# MicroSDcard.net
KiCad netlist of a schematic drawn in Altium Designer
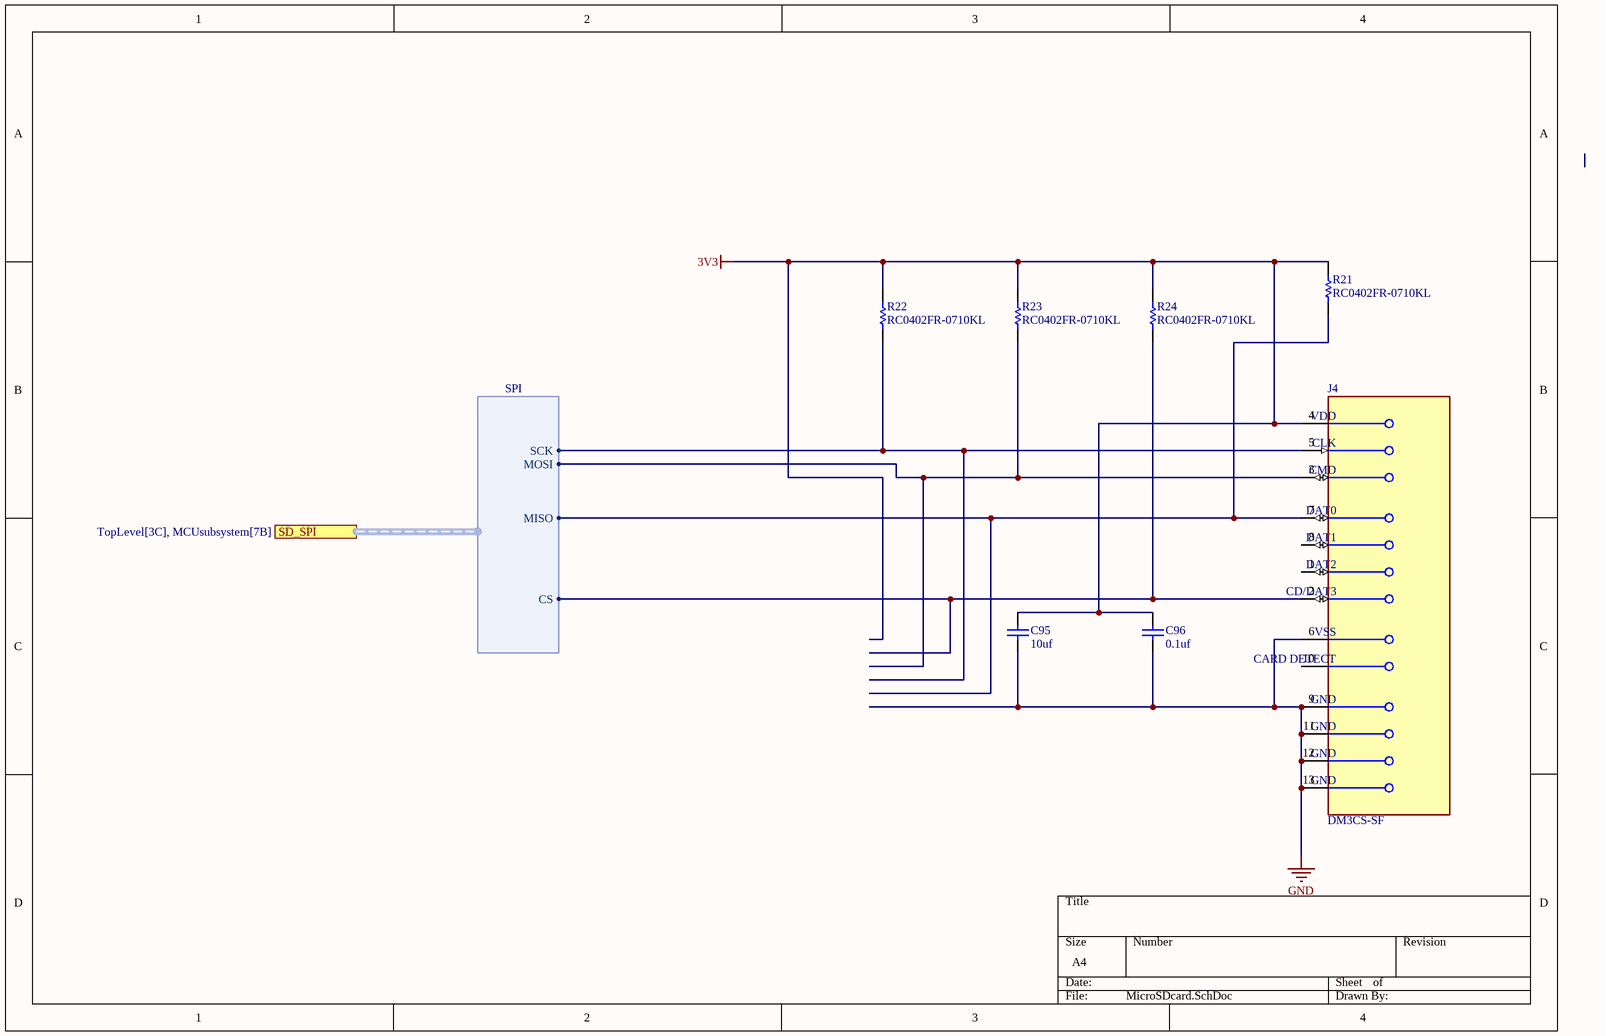
[diagram p0: MicroSDcard.SchDoc]

(export (version "E")
  (design (tool "Eeschema 10.0.6"))
  (components
    (comp (ref "C95")
      (value "10uf")
      (footprint "CAPC1005X56X25NL10T15")
      (fields
        (field (name "PART NUMBER") "0402ZD225MAT2A")
        (field (name "MANUFACTURER") "AVX Interconnect / Elco")
      )
      (libsource (lib "Altium Content Vault") (part "CAP"))
    )
    (comp (ref "C96")
      (value "0.1uf")
      (footprint "CAPC1608X90X35LL15T15")
      (description "Chip Capacitor, 100 nF, 25 V, -30 to 85 degC, 0603 (1608 Metric), RoHS, Tape and Reel")
      (fields (field (name "MANUFACTURER") "AVX"))
      (libsource (lib "Altium Content Vault") (part "CAP-NP-2"))
    )
    (comp (ref "J4")
      (value "DM3CS-SF")
      (footprint "FP-DM3CS-SF-MFG")
      (description "CONN MICRO SD CARD HINGED TYPE")
      (libsource (lib "Altium Content Vault") (part "bac915de5305cfdd1ca301aae530106"))
    )
    (comp (ref "R21")
      (value "RC0402FR-0710KL")
      (footprint "RESC1005X40X25LL05T10")
      (fields (field (name "MANUFACTURER") "Yageo / Phycomp"))
      (libsource (lib "Altium Content Vault") (part "RES"))
    )
    (comp (ref "R22")
      (value "RC0402FR-0710KL")
      (footprint "RESC1005X40X25LL05T10")
      (fields (field (name "MANUFACTURER") "Yageo / Phycomp"))
      (libsource (lib "Altium Content Vault") (part "RES"))
    )
    (comp (ref "R23")
      (value "RC0402FR-0710KL")
      (footprint "RESC1005X40X25LL05T10")
      (fields (field (name "MANUFACTURER") "Yageo / Phycomp"))
      (libsource (lib "Altium Content Vault") (part "RES"))
    )
    (comp (ref "R24")
      (value "RC0402FR-0710KL")
      (footprint "RESC1005X40X25LL05T10")
      (fields (field (name "MANUFACTURER") "Yageo / Phycomp"))
      (libsource (lib "Altium Content Vault") (part "RES"))
    )
  )
  (nets
    (net (code "3") (name "3V3") (class "Default")
      (node (ref "C95") (pin "1") (pinfunction "1_1") (pintype "passive"))
      (node (ref "C96") (pin "2") (pinfunction "2_2") (pintype "passive"))
      (node (ref "J4") (pin "4") (pinfunction "VDD_4") (pintype "power_in"))
      (node (ref "R21") (pin "2") (pinfunction "2_2") (pintype "passive"))
      (node (ref "R22") (pin "2") (pinfunction "2_2") (pintype "passive"))
      (node (ref "R23") (pin "2") (pinfunction "2_2") (pintype "passive"))
      (node (ref "R24") (pin "2") (pinfunction "2_2") (pintype "passive"))
    )
    (net (code "4") (name "GND") (class "Default")
      (node (ref "C95") (pin "2") (pinfunction "2_2") (pintype "passive"))
      (node (ref "C96") (pin "1") (pinfunction "1_1") (pintype "passive"))
      (node (ref "J4") (pin "11") (pinfunction "GND_11") (pintype "power_in"))
      (node (ref "J4") (pin "12") (pinfunction "GND_12") (pintype "power_in"))
      (node (ref "J4") (pin "13") (pinfunction "GND_13") (pintype "power_in"))
      (node (ref "J4") (pin "6") (pinfunction "VSS_6") (pintype "power_in"))
      (node (ref "J4") (pin "9") (pinfunction "GND_9") (pintype "power_in"))
    )
    (net (code "5") (name "Net-(J4-CD{slash}DAT3)") (class "Default")
      (node (ref "J4") (pin "2") (pinfunction "CD/DAT3_2") (pintype "bidirectional"))
      (node (ref "R24") (pin "1") (pinfunction "1_1") (pintype "passive"))
    )
    (net (code "6") (name "Net-(J4-CLK)") (class "Default")
      (node (ref "J4") (pin "5") (pinfunction "CLK_5") (pintype "input"))
      (node (ref "R22") (pin "1") (pinfunction "1_1") (pintype "passive"))
    )
    (net (code "7") (name "Net-(J4-CMD)") (class "Default")
      (node (ref "J4") (pin "3") (pinfunction "CMD_3") (pintype "bidirectional"))
      (node (ref "R23") (pin "1") (pinfunction "1_1") (pintype "passive"))
    )
    (net (code "8") (name "Net-(J4-DAT0)") (class "Default")
      (node (ref "J4") (pin "7") (pinfunction "DAT0_7") (pintype "bidirectional"))
      (node (ref "R21") (pin "1") (pinfunction "1_1") (pintype "passive"))
    )
    (net (code "9") (name "unconnected-(J4-CARD_DETECT-Pad10)") (class "Default")
      (node (ref "J4") (pin "10") (pinfunction "CARD_DETECT_10") (pintype "passive"))
    )
    (net (code "10") (name "unconnected-(J4-DAT1-Pad8)") (class "Default")
      (node (ref "J4") (pin "8") (pinfunction "DAT1_8") (pintype "bidirectional"))
    )
    (net (code "11") (name "unconnected-(J4-DAT2-Pad1)") (class "Default")
      (node (ref "J4") (pin "1") (pinfunction "DAT2_1") (pintype "bidirectional"))
    )
  )
)
